# 5_-USB2_TYPEC_USIC.net
KiCad netlist of a schematic drawn in Altium Designer
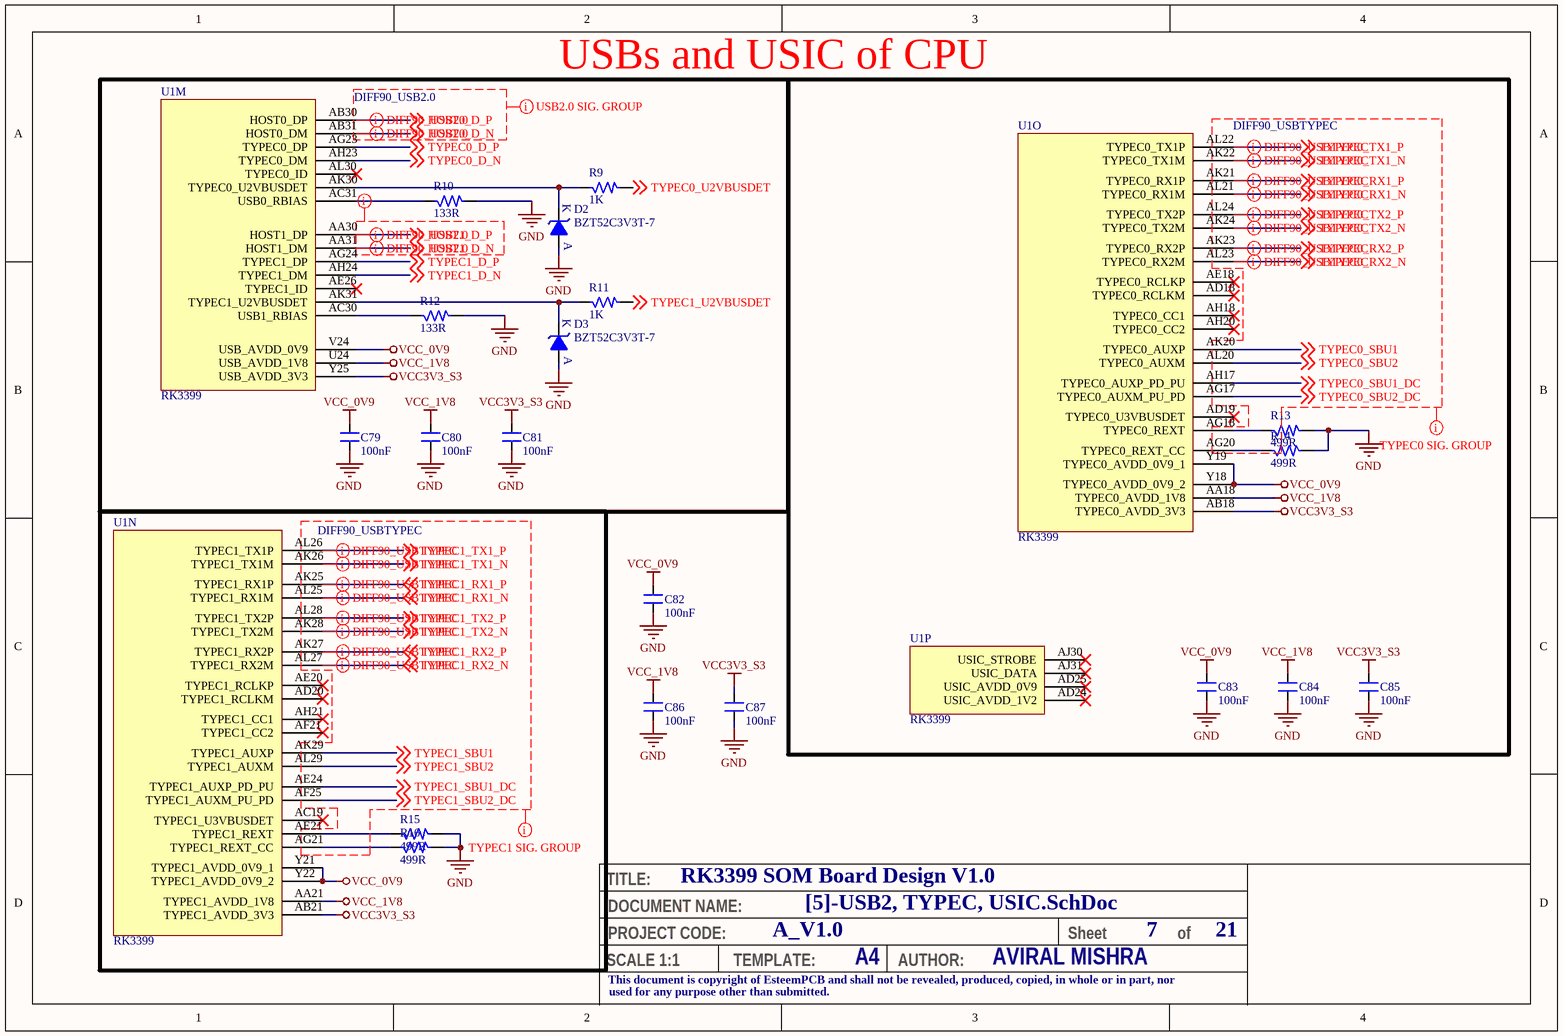
[diagram p0: [5]-USB2, TYPEC, USIC.SchDoc]

(export (version "E")
  (design (tool "Eeschema 10.0.6"))
  (components
    (comp (ref "C79")
      (value "100nF")
      (footprint "CAP_0201")
      (description "0.1µF ±10% 25V Ceramic Capacitor X5R 0201 (0603 Metric)")
      (fields
        (field (name "MANUFACTURER") "TDK Corporation")
        (field (name "MANUFACTURER PART NUMBER") "C0603X5R1E104K030BB")
      )
      (libsource (lib "RK3399 _Module_Intlib") (part "CAP_100nF-25V-10%-0201"))
    )
    (comp (ref "C80")
      (value "100nF")
      (footprint "CAP_0201")
      (description "0.1µF ±10% 25V Ceramic Capacitor X5R 0201 (0603 Metric)")
      (fields
        (field (name "MANUFACTURER") "TDK Corporation")
        (field (name "MANUFACTURER PART NUMBER") "C0603X5R1E104K030BB")
      )
      (libsource (lib "RK3399 _Module_Intlib") (part "CAP_100nF-25V-10%-0201"))
    )
    (comp (ref "C81")
      (value "100nF")
      (footprint "CAP_0201")
      (description "0.1µF ±10% 25V Ceramic Capacitor X5R 0201 (0603 Metric)")
      (fields
        (field (name "MANUFACTURER") "TDK Corporation")
        (field (name "MANUFACTURER PART NUMBER") "C0603X5R1E104K030BB")
      )
      (libsource (lib "RK3399 _Module_Intlib") (part "CAP_100nF-25V-10%-0201"))
    )
    (comp (ref "C82")
      (value "100nF")
      (footprint "CAP_0201")
      (description "0.1µF ±10% 25V Ceramic Capacitor X5R 0201 (0603 Metric)")
      (fields
        (field (name "MANUFACTURER") "TDK Corporation")
        (field (name "MANUFACTURER PART NUMBER") "C0603X5R1E104K030BB")
      )
      (libsource (lib "RK3399 _Module_Intlib") (part "CAP_100nF-25V-10%-0201"))
    )
    (comp (ref "C83")
      (value "100nF")
      (footprint "CAP_0201")
      (description "0.1µF ±10% 25V Ceramic Capacitor X5R 0201 (0603 Metric)")
      (fields
        (field (name "MANUFACTURER") "TDK Corporation")
        (field (name "MANUFACTURER PART NUMBER") "C0603X5R1E104K030BB")
      )
      (libsource (lib "RK3399 _Module_Intlib") (part "CAP_100nF-25V-10%-0201"))
    )
    (comp (ref "C84")
      (value "100nF")
      (footprint "CAP_0201")
      (description "0.1µF ±10% 25V Ceramic Capacitor X5R 0201 (0603 Metric)")
      (fields
        (field (name "MANUFACTURER") "TDK Corporation")
        (field (name "MANUFACTURER PART NUMBER") "C0603X5R1E104K030BB")
      )
      (libsource (lib "RK3399 _Module_Intlib") (part "CAP_100nF-25V-10%-0201"))
    )
    (comp (ref "C85")
      (value "100nF")
      (footprint "CAP_0201")
      (description "0.1µF ±10% 25V Ceramic Capacitor X5R 0201 (0603 Metric)")
      (fields
        (field (name "MANUFACTURER") "TDK Corporation")
        (field (name "MANUFACTURER PART NUMBER") "C0603X5R1E104K030BB")
      )
      (libsource (lib "RK3399 _Module_Intlib") (part "CAP_100nF-25V-10%-0201"))
    )
    (comp (ref "C86")
      (value "100nF")
      (footprint "CAP_0201")
      (description "0.1µF ±10% 25V Ceramic Capacitor X5R 0201 (0603 Metric)")
      (fields
        (field (name "MANUFACTURER") "TDK Corporation")
        (field (name "MANUFACTURER PART NUMBER") "C0603X5R1E104K030BB")
      )
      (libsource (lib "RK3399 _Module_Intlib") (part "CAP_100nF-25V-10%-0201"))
    )
    (comp (ref "C87")
      (value "100nF")
      (footprint "CAP_0201")
      (description "0.1µF ±10% 25V Ceramic Capacitor X5R 0201 (0603 Metric)")
      (fields
        (field (name "MANUFACTURER") "TDK Corporation")
        (field (name "MANUFACTURER PART NUMBER") "C0603X5R1E104K030BB")
      )
      (libsource (lib "RK3399 _Module_Intlib") (part "CAP_100nF-25V-10%-0201"))
    )
    (comp (ref "D2")
      (value "BZT52C3V3T-7")
      (footprint "DIO_SOD523")
      (description "Zener Diode 3.3V 300mW ±6% Surface Mount SOD-523")
      (fields (field (name "MANUFACTURER") "Diodes Incorporated"))
      (libsource (lib "RK3399 _Module_Schlib") (part "DIO-Z_3.3V-300mW-SOD-523"))
    )
    (comp (ref "D3")
      (value "BZT52C3V3T-7")
      (footprint "DIO_SOD523")
      (description "Zener Diode 3.3V 300mW ±6% Surface Mount SOD-523")
      (fields (field (name "MANUFACTURER") "Diodes Incorporated"))
      (libsource (lib "RK3399 _Module_Schlib") (part "DIO-Z_3.3V-300mW-SOD-523"))
    )
    (comp (ref "R9")
      (value "1K")
      (footprint "RES_0201")
      (description "1 kOhms ±1% 0.05W, 1/20W Chip Resistor 0201 (0603 Metric) Thick Film")
      (fields
        (field (name "MANUFACTURER") "Yageo")
        (field (name "MANUFACTURER PART NUMBER") "RC0201FR-071KL")
      )
      (libsource (lib "RK3399 _Module_Intlib") (part "RES_1K-0.05W-1%-0201"))
    )
    (comp (ref "R10")
      (value "133R")
      (footprint "RES_0201")
      (description "133 Ohms ±1% 0.05W, 1/20W Chip Resistor 0201 (0603 Metric) Automotive AEC-Q200 Thick Film")
      (fields
        (field (name "MANUFACTURER") "Panasonic Electronic Components")
        (field (name "MANUFACTURER PART NUMBER") "ERJ-1GNF1330C")
      )
      (libsource (lib "RK3399 _Module_Intlib") (part "RES_133R-0.05W-1%-0201"))
    )
    (comp (ref "R11")
      (value "1K")
      (footprint "RES_0201")
      (description "1 kOhms ±1% 0.05W, 1/20W Chip Resistor 0201 (0603 Metric) Thick Film")
      (fields
        (field (name "MANUFACTURER") "Yageo")
        (field (name "MANUFACTURER PART NUMBER") "RC0201FR-071KL")
      )
      (libsource (lib "RK3399 _Module_Intlib") (part "RES_1K-0.05W-1%-0201"))
    )
    (comp (ref "R12")
      (value "133R")
      (footprint "RES_0201")
      (description "133 Ohms ±1% 0.05W, 1/20W Chip Resistor 0201 (0603 Metric) Automotive AEC-Q200 Thick Film")
      (fields
        (field (name "MANUFACTURER") "Panasonic Electronic Components")
        (field (name "MANUFACTURER PART NUMBER") "ERJ-1GNF1330C")
      )
      (libsource (lib "RK3399 _Module_Intlib") (part "RES_133R-0.05W-1%-0201"))
    )
    (comp (ref "R13")
      (value "499R")
      (footprint "RES_0201")
      (description "499 Ohms ±1% 0.05W, 1/20W Chip Resistor 0201 (0603 Metric) Thick Film")
      (fields
        (field (name "MANUFACTURER") "Stackpole Electronics Inc")
        (field (name "MANUFACTURER PART NUMBER") "RMCF0201FT499R")
      )
      (libsource (lib "RK3399 _Module_Intlib") (part "RES_499R-0.05W-1%-0201"))
    )
    (comp (ref "R14")
      (value "499R")
      (footprint "RES_0201")
      (description "499 Ohms ±1% 0.05W, 1/20W Chip Resistor 0201 (0603 Metric) Thick Film")
      (fields
        (field (name "MANUFACTURER") "Stackpole Electronics Inc")
        (field (name "MANUFACTURER PART NUMBER") "RMCF0201FT499R")
      )
      (libsource (lib "RK3399 _Module_Intlib") (part "RES_499R-0.05W-1%-0201"))
    )
    (comp (ref "R15")
      (value "499R")
      (footprint "RES_0201")
      (description "499 Ohms ±1% 0.05W, 1/20W Chip Resistor 0201 (0603 Metric) Thick Film")
      (fields
        (field (name "MANUFACTURER") "Stackpole Electronics Inc")
        (field (name "MANUFACTURER PART NUMBER") "RMCF0201FT499R")
      )
      (libsource (lib "RK3399 _Module_Intlib") (part "RES_499R-0.05W-1%-0201"))
    )
    (comp (ref "R16")
      (value "499R")
      (footprint "RES_0201")
      (description "499 Ohms ±1% 0.05W, 1/20W Chip Resistor 0201 (0603 Metric) Thick Film")
      (fields
        (field (name "MANUFACTURER") "Stackpole Electronics Inc")
        (field (name "MANUFACTURER PART NUMBER") "RMCF0201FT499R")
      )
      (libsource (lib "RK3399 _Module_Intlib") (part "RES_499R-0.05W-1%-0201"))
    )
    (comp (ref "U1")
      (value "RK3399")
      (footprint "FBGA828_23_826X826")
      (description "RK3399 is a low power, high performance processor for computing, personal mobile.")
      (fields (field (name "MANUFACTURER") "Rockchip"))
      (libsource (lib "RK3399 _Module_Schlib") (part "IC_RK3399-FCBGA828"))
    )
  )
  (nets
    (net (code "1") (name "GND") (class "Default")
      (node (ref "C79") (pin "2") (pinfunction "2_2") (pintype "passive"))
      (node (ref "C80") (pin "1") (pinfunction "1_1") (pintype "passive"))
      (node (ref "C81") (pin "1") (pinfunction "1_1") (pintype "passive"))
      (node (ref "C82") (pin "1") (pinfunction "1_1") (pintype "passive"))
      (node (ref "C83") (pin "1") (pinfunction "1_1") (pintype "passive"))
      (node (ref "C84") (pin "1") (pinfunction "1_1") (pintype "passive"))
      (node (ref "C85") (pin "1") (pinfunction "1_1") (pintype "passive"))
      (node (ref "C86") (pin "1") (pinfunction "1_1") (pintype "passive"))
      (node (ref "C87") (pin "1") (pinfunction "1_1") (pintype "passive"))
      (node (ref "D2") (pin "A") (pinfunction "A_A") (pintype "passive"))
      (node (ref "D3") (pin "A") (pinfunction "A_A") (pintype "passive"))
      (node (ref "R10") (pin "2") (pinfunction "2_2") (pintype "passive"))
      (node (ref "R12") (pin "2") (pinfunction "2_2") (pintype "passive"))
      (node (ref "R13") (pin "2") (pinfunction "2_2") (pintype "passive"))
      (node (ref "R14") (pin "2") (pinfunction "2_2") (pintype "passive"))
      (node (ref "R15") (pin "2") (pinfunction "2_2") (pintype "passive"))
      (node (ref "R16") (pin "2") (pinfunction "2_2") (pintype "passive"))
    )
    (net (code "2") (name "HOST0_D_N") (class "Default")
      (node (ref "U1") (pin "AB31") (pinfunction "HOST0_DM_AB31") (pintype "passive"))
    )
    (net (code "3") (name "HOST0_D_P") (class "Default")
      (node (ref "U1") (pin "AB30") (pinfunction "HOST0_DP_AB30") (pintype "passive"))
    )
    (net (code "4") (name "HOST1_D_N") (class "Default")
      (node (ref "U1") (pin "AA31") (pinfunction "HOST1_DM_AA31") (pintype "passive"))
    )
    (net (code "5") (name "HOST1_D_P") (class "Default")
      (node (ref "U1") (pin "AA30") (pinfunction "HOST1_DP_AA30") (pintype "passive"))
    )
    (net (code "6") (name "Net-(U1M-TYPEC0_U2VBUSDET)") (class "Default")
      (node (ref "D2") (pin "K") (pinfunction "K_K") (pintype "passive"))
      (node (ref "R9") (pin "1") (pinfunction "1_1") (pintype "passive"))
      (node (ref "U1") (pin "AK30") (pinfunction "TYPEC0_U2VBUSDET_AK30") (pintype "passive"))
    )
    (net (code "7") (name "Net-(U1M-TYPEC1_U2VBUSDET)") (class "Default")
      (node (ref "D3") (pin "K") (pinfunction "K_K") (pintype "passive"))
      (node (ref "R11") (pin "1") (pinfunction "1_1") (pintype "passive"))
      (node (ref "U1") (pin "AK31") (pinfunction "TYPEC1_U2VBUSDET_AK31") (pintype "passive"))
    )
    (net (code "8") (name "Net-(U1M-USB0_RBIAS)") (class "Default")
      (node (ref "R10") (pin "1") (pinfunction "1_1") (pintype "passive"))
      (node (ref "U1") (pin "AC31") (pinfunction "USB0_RBIAS_AC31") (pintype "passive"))
    )
    (net (code "9") (name "Net-(U1M-USB1_RBIAS)") (class "Default")
      (node (ref "R12") (pin "1") (pinfunction "1_1") (pintype "passive"))
      (node (ref "U1") (pin "AC30") (pinfunction "USB1_RBIAS_AC30") (pintype "passive"))
    )
    (net (code "10") (name "Net-(U1N-TYPEC1_REXT)") (class "Default")
      (node (ref "R15") (pin "1") (pinfunction "1_1") (pintype "passive"))
      (node (ref "U1") (pin "AE21") (pinfunction "TYPEC1_REXT_AE21") (pintype "passive"))
    )
    (net (code "11") (name "Net-(U1N-TYPEC1_REXT_CC)") (class "Default")
      (node (ref "R16") (pin "1") (pinfunction "1_1") (pintype "passive"))
      (node (ref "U1") (pin "AG21") (pinfunction "TYPEC1_REXT_CC_AG21") (pintype "passive"))
    )
    (net (code "12") (name "Net-(U1O-TYPEC0_REXT)") (class "Default")
      (node (ref "R13") (pin "1") (pinfunction "1_1") (pintype "passive"))
      (node (ref "U1") (pin "AG18") (pinfunction "TYPEC0_REXT_AG18") (pintype "passive"))
    )
    (net (code "13") (name "Net-(U1O-TYPEC0_REXT_CC)") (class "Default")
      (node (ref "R14") (pin "1") (pinfunction "1_1") (pintype "passive"))
      (node (ref "U1") (pin "AG20") (pinfunction "TYPEC0_REXT_CC_AG20") (pintype "passive"))
    )
    (net (code "14") (name "TYPEC0_D_N") (class "Default")
      (node (ref "U1") (pin "AH23") (pinfunction "TYPEC0_DM_AH23") (pintype "passive"))
    )
    (net (code "15") (name "TYPEC0_D_P") (class "Default")
      (node (ref "U1") (pin "AG23") (pinfunction "TYPEC0_DP_AG23") (pintype "passive"))
    )
    (net (code "16") (name "TYPEC0_RX1_N") (class "Default")
      (node (ref "U1") (pin "AL21") (pinfunction "TYPEC0_RX1M_AL21") (pintype "passive"))
    )
    (net (code "17") (name "TYPEC0_RX1_P") (class "Default")
      (node (ref "U1") (pin "AK21") (pinfunction "TYPEC0_RX1P_AK21") (pintype "passive"))
    )
    (net (code "18") (name "TYPEC0_RX2_N") (class "Default")
      (node (ref "U1") (pin "AL23") (pinfunction "TYPEC0_RX2M_AL23") (pintype "passive"))
    )
    (net (code "19") (name "TYPEC0_RX2_P") (class "Default")
      (node (ref "U1") (pin "AK23") (pinfunction "TYPEC0_RX2P_AK23") (pintype "passive"))
    )
    (net (code "20") (name "TYPEC0_SBU1") (class "Default")
      (node (ref "U1") (pin "AK20") (pinfunction "TYPEC0_AUXP_AK20") (pintype "passive"))
    )
    (net (code "21") (name "TYPEC0_SBU1_DC") (class "Default")
      (node (ref "U1") (pin "AH17") (pinfunction "TYPEC0_AUXP_PD_PU_AH17") (pintype "passive"))
    )
    (net (code "22") (name "TYPEC0_SBU2") (class "Default")
      (node (ref "U1") (pin "AL20") (pinfunction "TYPEC0_AUXM_AL20") (pintype "passive"))
    )
    (net (code "23") (name "TYPEC0_SBU2_DC") (class "Default")
      (node (ref "U1") (pin "AG17") (pinfunction "TYPEC0_AUXM_PU_PD_AG17") (pintype "passive"))
    )
    (net (code "24") (name "TYPEC0_TX1_N") (class "Default")
      (node (ref "U1") (pin "AK22") (pinfunction "TYPEC0_TX1M_AK22") (pintype "passive"))
    )
    (net (code "25") (name "TYPEC0_TX1_P") (class "Default")
      (node (ref "U1") (pin "AL22") (pinfunction "TYPEC0_TX1P_AL22") (pintype "passive"))
    )
    (net (code "26") (name "TYPEC0_TX2_N") (class "Default")
      (node (ref "U1") (pin "AK24") (pinfunction "TYPEC0_TX2M_AK24") (pintype "passive"))
    )
    (net (code "27") (name "TYPEC0_TX2_P") (class "Default")
      (node (ref "U1") (pin "AL24") (pinfunction "TYPEC0_TX2P_AL24") (pintype "passive"))
    )
    (net (code "28") (name "TYPEC0_U2VBUSDET") (class "Default")
      (node (ref "R9") (pin "2") (pinfunction "2_2") (pintype "passive"))
    )
    (net (code "29") (name "TYPEC1_D_N") (class "Default")
      (node (ref "U1") (pin "AH24") (pinfunction "TYPEC1_DM_AH24") (pintype "passive"))
    )
    (net (code "30") (name "TYPEC1_D_P") (class "Default")
      (node (ref "U1") (pin "AG24") (pinfunction "TYPEC1_DP_AG24") (pintype "passive"))
    )
    (net (code "31") (name "TYPEC1_RX1_N") (class "Default")
      (node (ref "U1") (pin "AL25") (pinfunction "TYPEC1_RX1M_AL25") (pintype "passive"))
    )
    (net (code "32") (name "TYPEC1_RX1_P") (class "Default")
      (node (ref "U1") (pin "AK25") (pinfunction "TYPEC1_RX1P_AK25") (pintype "passive"))
    )
    (net (code "33") (name "TYPEC1_RX2_N") (class "Default")
      (node (ref "U1") (pin "AL27") (pinfunction "TYPEC1_RX2M_AL27") (pintype "passive"))
    )
    (net (code "34") (name "TYPEC1_RX2_P") (class "Default")
      (node (ref "U1") (pin "AK27") (pinfunction "TYPEC1_RX2P_AK27") (pintype "passive"))
    )
    (net (code "35") (name "TYPEC1_SBU1") (class "Default")
      (node (ref "U1") (pin "AK29") (pinfunction "TYPEC1_AUXP_AK29") (pintype "passive"))
    )
    (net (code "36") (name "TYPEC1_SBU1_DC") (class "Default")
      (node (ref "U1") (pin "AE24") (pinfunction "TYPEC1_AUXP_PD_PU_AE24") (pintype "passive"))
    )
    (net (code "37") (name "TYPEC1_SBU2") (class "Default")
      (node (ref "U1") (pin "AL29") (pinfunction "TYPEC1_AUXM_AL29") (pintype "passive"))
    )
    (net (code "38") (name "TYPEC1_SBU2_DC") (class "Default")
      (node (ref "U1") (pin "AF25") (pinfunction "TYPEC1_AUXM_PU_PD_AF25") (pintype "passive"))
    )
    (net (code "39") (name "TYPEC1_TX1_N") (class "Default")
      (node (ref "U1") (pin "AK26") (pinfunction "TYPEC1_TX1M_AK26") (pintype "passive"))
    )
    (net (code "40") (name "TYPEC1_TX1_P") (class "Default")
      (node (ref "U1") (pin "AL26") (pinfunction "TYPEC1_TX1P_AL26") (pintype "passive"))
    )
    (net (code "41") (name "TYPEC1_TX2_N") (class "Default")
      (node (ref "U1") (pin "AK28") (pinfunction "TYPEC1_TX2M_AK28") (pintype "passive"))
    )
    (net (code "42") (name "TYPEC1_TX2_P") (class "Default")
      (node (ref "U1") (pin "AL28") (pinfunction "TYPEC1_TX2P_AL28") (pintype "passive"))
    )
    (net (code "43") (name "TYPEC1_U2VBUSDET") (class "Default")
      (node (ref "R11") (pin "2") (pinfunction "2_2") (pintype "passive"))
    )
    (net (code "44") (name "VCC3V3_S3") (class "Default")
      (node (ref "C81") (pin "2") (pinfunction "2_2") (pintype "passive"))
      (node (ref "C85") (pin "2") (pinfunction "2_2") (pintype "passive"))
      (node (ref "C87") (pin "2") (pinfunction "2_2") (pintype "passive"))
      (node (ref "U1") (pin "AB18") (pinfunction "TYPEC0_AVDD_3V3_AB18") (pintype "passive"))
      (node (ref "U1") (pin "AB21") (pinfunction "TYPEC1_AVDD_3V3_AB21") (pintype "passive"))
      (node (ref "U1") (pin "Y25") (pinfunction "USB_AVDD_3V3_Y25") (pintype "passive"))
    )
    (net (code "45") (name "VCC_0V9") (class "Default")
      (node (ref "C79") (pin "1") (pinfunction "1_1") (pintype "passive"))
      (node (ref "C82") (pin "2") (pinfunction "2_2") (pintype "passive"))
      (node (ref "C83") (pin "2") (pinfunction "2_2") (pintype "passive"))
      (node (ref "U1") (pin "V24") (pinfunction "USB_AVDD_0V9_V24") (pintype "passive"))
      (node (ref "U1") (pin "Y18") (pinfunction "TYPEC0_AVDD_0V9_2_Y18") (pintype "passive"))
      (node (ref "U1") (pin "Y19") (pinfunction "TYPEC0_AVDD_0V9_1_Y19") (pintype "passive"))
      (node (ref "U1") (pin "Y21") (pinfunction "TYPEC1_AVDD_0V9_1_Y21") (pintype "passive"))
      (node (ref "U1") (pin "Y22") (pinfunction "TYPEC1_AVDD_0V9_2_Y22") (pintype "passive"))
    )
    (net (code "46") (name "VCC_1V8") (class "Default")
      (node (ref "C80") (pin "2") (pinfunction "2_2") (pintype "passive"))
      (node (ref "C84") (pin "2") (pinfunction "2_2") (pintype "passive"))
      (node (ref "C86") (pin "2") (pinfunction "2_2") (pintype "passive"))
      (node (ref "U1") (pin "AA18") (pinfunction "TYPEC0_AVDD_1V8_AA18") (pintype "passive"))
      (node (ref "U1") (pin "AA21") (pinfunction "TYPEC1_AVDD_1V8_AA21") (pintype "passive"))
      (node (ref "U1") (pin "U24") (pinfunction "USB_AVDD_1V8_U24") (pintype "passive"))
    )
    (net (code "47") (name "unconnected-(U1M-TYPEC0_ID-PadAL30)") (class "Default")
      (node (ref "U1") (pin "AL30") (pinfunction "TYPEC0_ID_AL30") (pintype "passive+no_connect"))
    )
    (net (code "48") (name "unconnected-(U1M-TYPEC1_ID-PadAE26)") (class "Default")
      (node (ref "U1") (pin "AE26") (pinfunction "TYPEC1_ID_AE26") (pintype "passive+no_connect"))
    )
    (net (code "49") (name "unconnected-(U1N-TYPEC1_CC1-PadAH21)") (class "Default")
      (node (ref "U1") (pin "AH21") (pinfunction "TYPEC1_CC1_AH21") (pintype "passive+no_connect"))
    )
    (net (code "50") (name "unconnected-(U1N-TYPEC1_CC2-PadAF21)") (class "Default")
      (node (ref "U1") (pin "AF21") (pinfunction "TYPEC1_CC2_AF21") (pintype "passive+no_connect"))
    )
    (net (code "51") (name "unconnected-(U1N-TYPEC1_RCLKM-PadAD20)") (class "Default")
      (node (ref "U1") (pin "AD20") (pinfunction "TYPEC1_RCLKM_AD20") (pintype "passive+no_connect"))
    )
    (net (code "52") (name "unconnected-(U1N-TYPEC1_RCLKP-PadAE20)") (class "Default")
      (node (ref "U1") (pin "AE20") (pinfunction "TYPEC1_RCLKP_AE20") (pintype "passive+no_connect"))
    )
    (net (code "53") (name "unconnected-(U1N-TYPEC1_U3VBUSDET-PadAC19)") (class "Default")
      (node (ref "U1") (pin "AC19") (pinfunction "TYPEC1_U3VBUSDET_AC19") (pintype "passive+no_connect"))
    )
    (net (code "54") (name "unconnected-(U1O-TYPEC0_CC1-PadAH18)") (class "Default")
      (node (ref "U1") (pin "AH18") (pinfunction "TYPEC0_CC1_AH18") (pintype "passive+no_connect"))
    )
    (net (code "55") (name "unconnected-(U1O-TYPEC0_CC2-PadAH20)") (class "Default")
      (node (ref "U1") (pin "AH20") (pinfunction "TYPEC0_CC2_AH20") (pintype "passive+no_connect"))
    )
    (net (code "56") (name "unconnected-(U1O-TYPEC0_RCLKM-PadAD18)") (class "Default")
      (node (ref "U1") (pin "AD18") (pinfunction "TYPEC0_RCLKM_AD18") (pintype "passive+no_connect"))
    )
    (net (code "57") (name "unconnected-(U1O-TYPEC0_RCLKP-PadAE18)") (class "Default")
      (node (ref "U1") (pin "AE18") (pinfunction "TYPEC0_RCLKP_AE18") (pintype "passive+no_connect"))
    )
    (net (code "58") (name "unconnected-(U1O-TYPEC0_U3VBUSDET-PadAD19)") (class "Default")
      (node (ref "U1") (pin "AD19") (pinfunction "TYPEC0_U3VBUSDET_AD19") (pintype "passive+no_connect"))
    )
    (net (code "59") (name "unconnected-(U1P-USIC_AVDD_0V9-PadAD25)") (class "Default")
      (node (ref "U1") (pin "AD25") (pinfunction "USIC_AVDD_0V9_AD25") (pintype "passive+no_connect"))
    )
    (net (code "60") (name "unconnected-(U1P-USIC_AVDD_1V2-PadAD24)") (class "Default")
      (node (ref "U1") (pin "AD24") (pinfunction "USIC_AVDD_1V2_AD24") (pintype "passive+no_connect"))
    )
    (net (code "61") (name "unconnected-(U1P-USIC_DATA-PadAJ31)") (class "Default")
      (node (ref "U1") (pin "AJ31") (pinfunction "USIC_DATA_AJ31") (pintype "passive+no_connect"))
    )
    (net (code "62") (name "unconnected-(U1P-USIC_STROBE-PadAJ30)") (class "Default")
      (node (ref "U1") (pin "AJ30") (pinfunction "USIC_STROBE_AJ30") (pintype "passive+no_connect"))
    )
  )
)
